# OpenPack_BATMOD_V1p0_MAN.net
KiCad netlist of a schematic drawn in Altium Designer
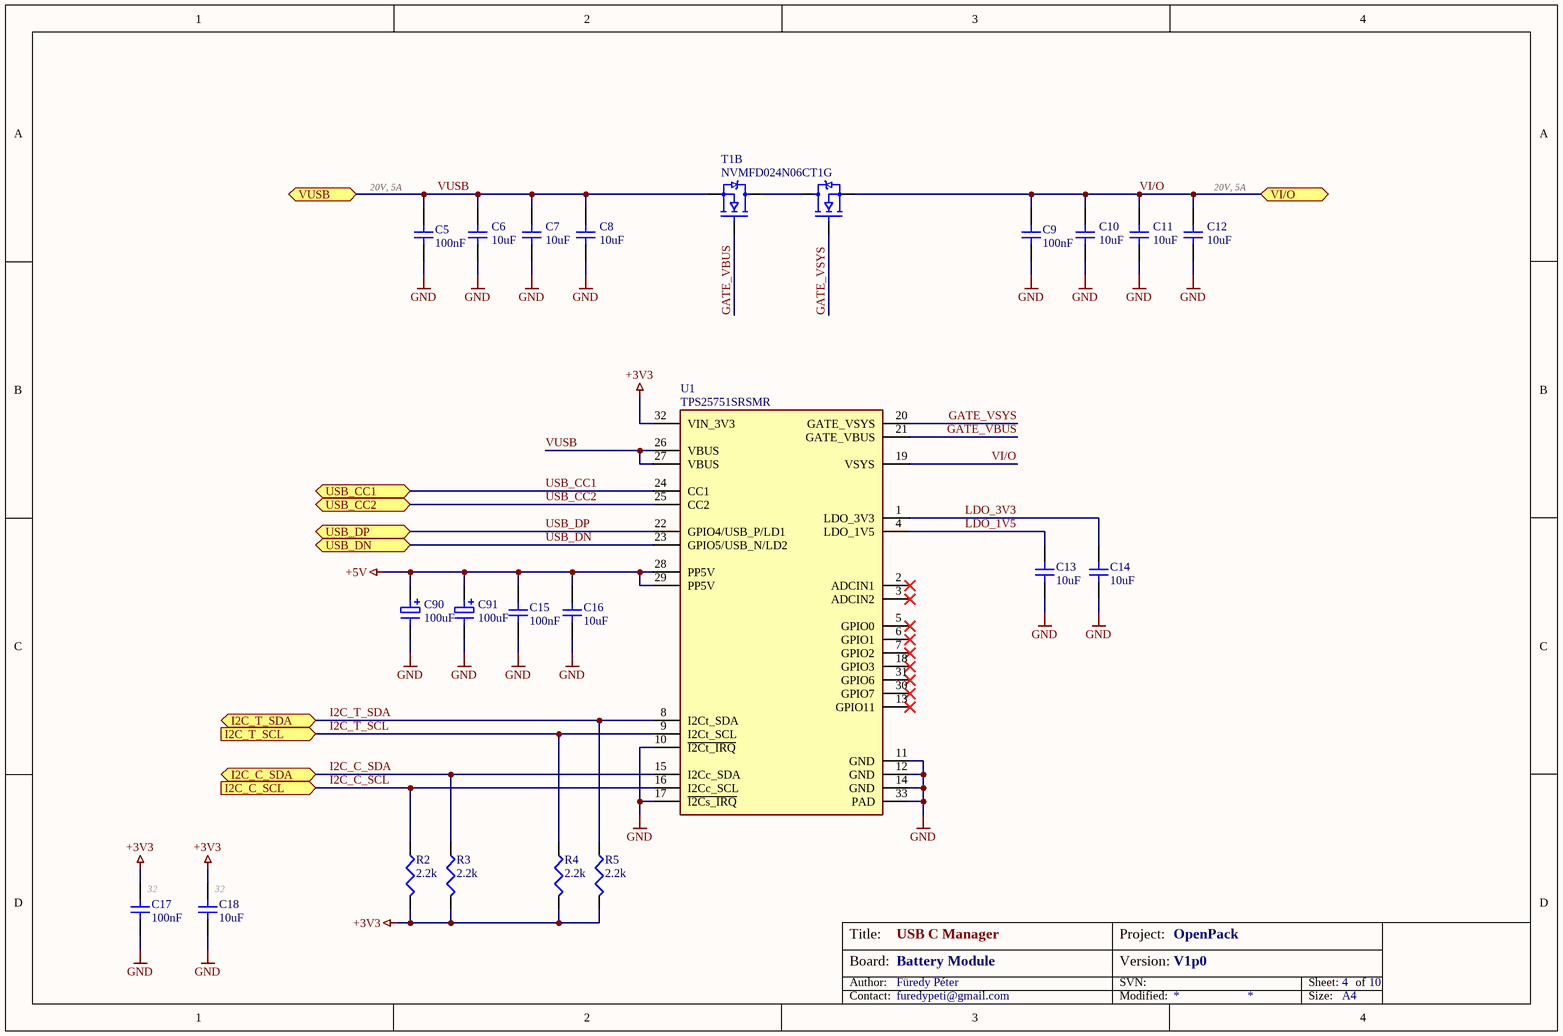
[diagram p0: OpenPack_BATMOD_V1p0_MAN.SchDoc]

(export (version "E")
  (design (tool "Eeschema 10.0.6"))
  (components
    (comp (ref "C5")
      (value "100nF")
      (footprint "CAP_0603")
      (description "MLCC capacitor")
      (libsource (lib "SCHLIB") (part "NP-CAPACITOR"))
    )
    (comp (ref "C6")
      (value "10uF")
      (footprint "CAP_1210")
      (description "UMK325BJ106KM-P")
      (fields (field (name "PART NUMBER") "810-CGA6P1X7R1N106K2"))
      (libsource (lib "SCHLIB") (part "NP-CAPACITOR"))
    )
    (comp (ref "C7")
      (value "10uF")
      (footprint "CAP_1210")
      (description "UMK325BJ106KM-P")
      (fields (field (name "PART NUMBER") "810-CGA6P1X7R1N106K2"))
      (libsource (lib "SCHLIB") (part "NP-CAPACITOR"))
    )
    (comp (ref "C8")
      (value "10uF")
      (footprint "CAP_1210")
      (description "UMK325BJ106KM-P")
      (fields (field (name "PART NUMBER") "810-CGA6P1X7R1N106K2"))
      (libsource (lib "SCHLIB") (part "NP-CAPACITOR"))
    )
    (comp (ref "C9")
      (value "100nF")
      (footprint "CAP_0603")
      (description "MLCC capacitor")
      (libsource (lib "SCHLIB") (part "NP-CAPACITOR"))
    )
    (comp (ref "C10")
      (value "10uF")
      (footprint "CAP_1210")
      (description "UMK325BJ106KM-P")
      (fields (field (name "PART NUMBER") "810-CGA6P1X7R1N106K2"))
      (libsource (lib "SCHLIB") (part "NP-CAPACITOR"))
    )
    (comp (ref "C11")
      (value "10uF")
      (footprint "CAP_1210")
      (description "UMK325BJ106KM-P")
      (fields (field (name "PART NUMBER") "810-CGA6P1X7R1N106K2"))
      (libsource (lib "SCHLIB") (part "NP-CAPACITOR"))
    )
    (comp (ref "C12")
      (value "10uF")
      (footprint "CAP_1210")
      (description "UMK325BJ106KM-P")
      (fields (field (name "PART NUMBER") "810-CGA6P1X7R1N106K2"))
      (libsource (lib "SCHLIB") (part "NP-CAPACITOR"))
    )
    (comp (ref "C13")
      (value "10uF")
      (footprint "CAP_0603")
      (description "MLCC capacitor")
      (libsource (lib "SCHLIB") (part "NP-CAPACITOR"))
    )
    (comp (ref "C14")
      (value "10uF")
      (footprint "CAP_0603")
      (description "MLCC capacitor")
      (libsource (lib "SCHLIB") (part "NP-CAPACITOR"))
    )
    (comp (ref "C15")
      (value "100nF")
      (footprint "CAP_0603")
      (description "MLCC capacitor")
      (libsource (lib "SCHLIB") (part "NP-CAPACITOR"))
    )
    (comp (ref "C16")
      (value "10uF")
      (footprint "CAP_0603")
      (description "MLCC capacitor")
      (libsource (lib "SCHLIB") (part "NP-CAPACITOR"))
    )
    (comp (ref "C17")
      (value "100nF")
      (footprint "CAP_0603")
      (description "MLCC capacitor")
      (libsource (lib "SCHLIB") (part "NP-CAPACITOR"))
    )
    (comp (ref "C18")
      (value "10uF")
      (footprint "CAP_0603")
      (description "MLCC capacitor")
      (libsource (lib "SCHLIB") (part "NP-CAPACITOR"))
    )
    (comp (ref "C90")
      (value "100uF")
      (footprint "CAP-SMD-6.3X7.7")
      (description "ELCO capacitor")
      (libsource (lib "SCHLIB") (part "P-CAPACITOR"))
    )
    (comp (ref "C91")
      (value "100uF")
      (footprint "CAP-SMD-6.3X7.7")
      (description "ELCO capacitor")
      (libsource (lib "SCHLIB") (part "P-CAPACITOR"))
    )
    (comp (ref "R2")
      (value "2.2k")
      (footprint "RES-0603")
      (description "Metal Film Resistor")
      (libsource (lib "SCHLIB") (part "RESISTOR"))
    )
    (comp (ref "R3")
      (value "2.2k")
      (footprint "RES-0603")
      (description "Metal Film Resistor")
      (libsource (lib "SCHLIB") (part "RESISTOR"))
    )
    (comp (ref "R4")
      (value "2.2k")
      (footprint "RES-0603")
      (description "Metal Film Resistor")
      (libsource (lib "SCHLIB") (part "RESISTOR"))
    )
    (comp (ref "R5")
      (value "2.2k")
      (footprint "RES-0603")
      (description "Metal Film Resistor")
      (libsource (lib "SCHLIB") (part "RESISTOR"))
    )
    (comp (ref "T1")
      (value "NVMFD024N06CT1G")
      (footprint "SO-8FL (DFN8)")
      (description "Power NMOSFET Dual, 60V, 24A, 22mΩ")
      (fields (field (name "PART NUMBER") "863-NVMFD024N06CT1G"))
      (libsource (lib "SCHLIB") (part "NVMFD024N06CT1G"))
    )
    (comp (ref "U1")
      (value "TPS25751SRSMR")
      (footprint "QFN32 - 0.4mm")
      (description "USB Interface IC USB Type-C and USB P ower Delivery (PD)")
      (fields (field (name "PART NUMBER") "595-TPS25751SRSMR"))
      (libsource (lib "SCHLIB") (part "TPS25751SRSMR"))
    )
  )
  (nets
    (net (code "1") (name "+3V3") (class "Default")
      (node (ref "C17") (pin "2") (pinfunction "2_2") (pintype "passive"))
      (node (ref "C18") (pin "2") (pinfunction "2_2") (pintype "passive"))
      (node (ref "R2") (pin "2") (pintype "passive"))
      (node (ref "R3") (pin "2") (pintype "passive"))
      (node (ref "R4") (pin "2") (pintype "passive"))
      (node (ref "R5") (pin "2") (pintype "passive"))
      (node (ref "U1") (pin "32") (pinfunction "VIN_3V3_32") (pintype "passive"))
    )
    (net (code "2") (name "+5V") (class "Default")
      (node (ref "C15") (pin "2") (pinfunction "2_2") (pintype "passive"))
      (node (ref "C16") (pin "2") (pinfunction "2_2") (pintype "passive"))
      (node (ref "C90") (pin "1") (pintype "passive"))
      (node (ref "C91") (pin "1") (pintype "passive"))
      (node (ref "U1") (pin "28") (pinfunction "PP5V_28") (pintype "passive"))
      (node (ref "U1") (pin "29") (pinfunction "PP5V_29") (pintype "passive"))
    )
    (net (code "3") (name "/GATE_VBUS") (class "Default")
      (node (ref "T1") (pin "4") (pinfunction "4_4") (pintype "passive"))
      (node (ref "U1") (pin "21") (pinfunction "GATE_VBUS_21") (pintype "passive"))
    )
    (net (code "4") (name "/GATE_VSYS") (class "Default")
      (node (ref "T1") (pin "2") (pinfunction "2_2") (pintype "passive"))
      (node (ref "U1") (pin "20") (pinfunction "GATE_VSYS_20") (pintype "passive"))
    )
    (net (code "5") (name "/I2C_C_SCL") (class "Default")
      (node (ref "R2") (pin "1") (pintype "passive"))
      (node (ref "U1") (pin "16") (pinfunction "I2Cc_SCL_16") (pintype "passive"))
    )
    (net (code "6") (name "/I2C_C_SDA") (class "Default")
      (node (ref "R3") (pin "1") (pintype "passive"))
      (node (ref "U1") (pin "15") (pinfunction "I2Cc_SDA_15") (pintype "passive"))
    )
    (net (code "7") (name "/I2C_T_SCL") (class "Default")
      (node (ref "R4") (pin "1") (pintype "passive"))
      (node (ref "U1") (pin "9") (pinfunction "I2Ct_SCL_9") (pintype "passive"))
    )
    (net (code "8") (name "/I2C_T_SDA") (class "Default")
      (node (ref "R5") (pin "1") (pintype "passive"))
      (node (ref "U1") (pin "8") (pinfunction "I2Ct_SDA_8") (pintype "passive"))
    )
    (net (code "9") (name "/LDO_1V5") (class "Default")
      (node (ref "C13") (pin "2") (pinfunction "2_2") (pintype "passive"))
      (node (ref "U1") (pin "4") (pinfunction "LDO_1V5_4") (pintype "passive"))
    )
    (net (code "10") (name "/LDO_3V3") (class "Default")
      (node (ref "C14") (pin "2") (pinfunction "2_2") (pintype "passive"))
      (node (ref "U1") (pin "1") (pinfunction "LDO_3V3_1") (pintype "passive"))
    )
    (net (code "11") (name "/USB_CC1") (class "Default")
      (node (ref "U1") (pin "24") (pinfunction "CC1_24") (pintype "passive"))
    )
    (net (code "12") (name "/USB_CC2") (class "Default")
      (node (ref "U1") (pin "25") (pinfunction "CC2_25") (pintype "passive"))
    )
    (net (code "13") (name "/USB_DN") (class "Default")
      (node (ref "U1") (pin "23") (pinfunction "GPIO5/USB_N/LD2_23") (pintype "passive"))
    )
    (net (code "14") (name "/USB_DP") (class "Default")
      (node (ref "U1") (pin "22") (pinfunction "GPIO4/USB_P/LD1_22") (pintype "passive"))
    )
    (net (code "15") (name "/VI{slash}O") (class "Default")
      (node (ref "C10") (pin "2") (pinfunction "2_2") (pintype "passive"))
      (node (ref "C11") (pin "2") (pinfunction "2_2") (pintype "passive"))
      (node (ref "C12") (pin "2") (pinfunction "2_2") (pintype "passive"))
      (node (ref "C9") (pin "2") (pinfunction "2_2") (pintype "passive"))
      (node (ref "T1") (pin "1") (pinfunction "1_1") (pintype "passive"))
      (node (ref "U1") (pin "19") (pinfunction "VSYS_19") (pintype "passive"))
    )
    (net (code "16") (name "/VUSB") (class "Default")
      (node (ref "C5") (pin "2") (pinfunction "2_2") (pintype "passive"))
      (node (ref "C6") (pin "2") (pinfunction "2_2") (pintype "passive"))
      (node (ref "C7") (pin "2") (pinfunction "2_2") (pintype "passive"))
      (node (ref "C8") (pin "2") (pinfunction "2_2") (pintype "passive"))
      (node (ref "T1") (pin "3") (pinfunction "3_3") (pintype "passive"))
      (node (ref "U1") (pin "26") (pinfunction "VBUS_26") (pintype "passive"))
      (node (ref "U1") (pin "27") (pinfunction "VBUS_27") (pintype "passive"))
    )
    (net (code "17") (name "GND") (class "Default")
      (node (ref "C10") (pin "1") (pinfunction "1_1") (pintype "passive"))
      (node (ref "C11") (pin "1") (pinfunction "1_1") (pintype "passive"))
      (node (ref "C12") (pin "1") (pinfunction "1_1") (pintype "passive"))
      (node (ref "C13") (pin "1") (pinfunction "1_1") (pintype "passive"))
      (node (ref "C14") (pin "1") (pinfunction "1_1") (pintype "passive"))
      (node (ref "C15") (pin "1") (pinfunction "1_1") (pintype "passive"))
      (node (ref "C16") (pin "1") (pinfunction "1_1") (pintype "passive"))
      (node (ref "C17") (pin "1") (pinfunction "1_1") (pintype "passive"))
      (node (ref "C18") (pin "1") (pinfunction "1_1") (pintype "passive"))
      (node (ref "C5") (pin "1") (pinfunction "1_1") (pintype "passive"))
      (node (ref "C6") (pin "1") (pinfunction "1_1") (pintype "passive"))
      (node (ref "C7") (pin "1") (pinfunction "1_1") (pintype "passive"))
      (node (ref "C8") (pin "1") (pinfunction "1_1") (pintype "passive"))
      (node (ref "C9") (pin "1") (pinfunction "1_1") (pintype "passive"))
      (node (ref "C90") (pin "2") (pintype "passive"))
      (node (ref "C91") (pin "2") (pintype "passive"))
      (node (ref "U1") (pin "10") (pinfunction "~{I2Ct_IRQ}_10") (pintype "passive"))
      (node (ref "U1") (pin "11") (pinfunction "GND_11") (pintype "passive"))
      (node (ref "U1") (pin "12") (pinfunction "GND_12") (pintype "passive"))
      (node (ref "U1") (pin "14") (pinfunction "GND_14") (pintype "passive"))
      (node (ref "U1") (pin "17") (pinfunction "~{I2Cs_IRQ}_17") (pintype "passive"))
      (node (ref "U1") (pin "33") (pinfunction "PAD_33") (pintype "passive"))
    )
    (net (code "18") (name "Net-(T1-Pad10)") (class "Default")
      (node (ref "T1") (pin "10") (pinfunction "10_10") (pintype "passive"))
      (node (ref "T1") (pin "9") (pinfunction "9_9") (pintype "passive"))
    )
    (net (code "19") (name "unconnected-(U1-ADCIN1-Pad2)") (class "Default")
      (node (ref "U1") (pin "2") (pinfunction "ADCIN1_2") (pintype "passive+no_connect"))
    )
    (net (code "20") (name "unconnected-(U1-ADCIN2-Pad3)") (class "Default")
      (node (ref "U1") (pin "3") (pinfunction "ADCIN2_3") (pintype "passive+no_connect"))
    )
    (net (code "21") (name "unconnected-(U1-GPIO0-Pad5)") (class "Default")
      (node (ref "U1") (pin "5") (pinfunction "GPIO0_5") (pintype "passive+no_connect"))
    )
    (net (code "22") (name "unconnected-(U1-GPIO1-Pad6)") (class "Default")
      (node (ref "U1") (pin "6") (pinfunction "GPIO1_6") (pintype "passive+no_connect"))
    )
    (net (code "23") (name "unconnected-(U1-GPIO2-Pad7)") (class "Default")
      (node (ref "U1") (pin "7") (pinfunction "GPIO2_7") (pintype "passive+no_connect"))
    )
    (net (code "24") (name "unconnected-(U1-GPIO3-Pad18)") (class "Default")
      (node (ref "U1") (pin "18") (pinfunction "GPIO3_18") (pintype "passive+no_connect"))
    )
    (net (code "25") (name "unconnected-(U1-GPIO6-Pad31)") (class "Default")
      (node (ref "U1") (pin "31") (pinfunction "GPIO6_31") (pintype "passive+no_connect"))
    )
    (net (code "26") (name "unconnected-(U1-GPIO7-Pad30)") (class "Default")
      (node (ref "U1") (pin "30") (pinfunction "GPIO7_30") (pintype "passive+no_connect"))
    )
    (net (code "27") (name "unconnected-(U1-GPIO11-Pad13)") (class "Default")
      (node (ref "U1") (pin "13") (pinfunction "GPIO11_13") (pintype "passive+no_connect"))
    )
  )
)
